# upperBoard.net
KiCad netlist of a schematic drawn in EAGLE
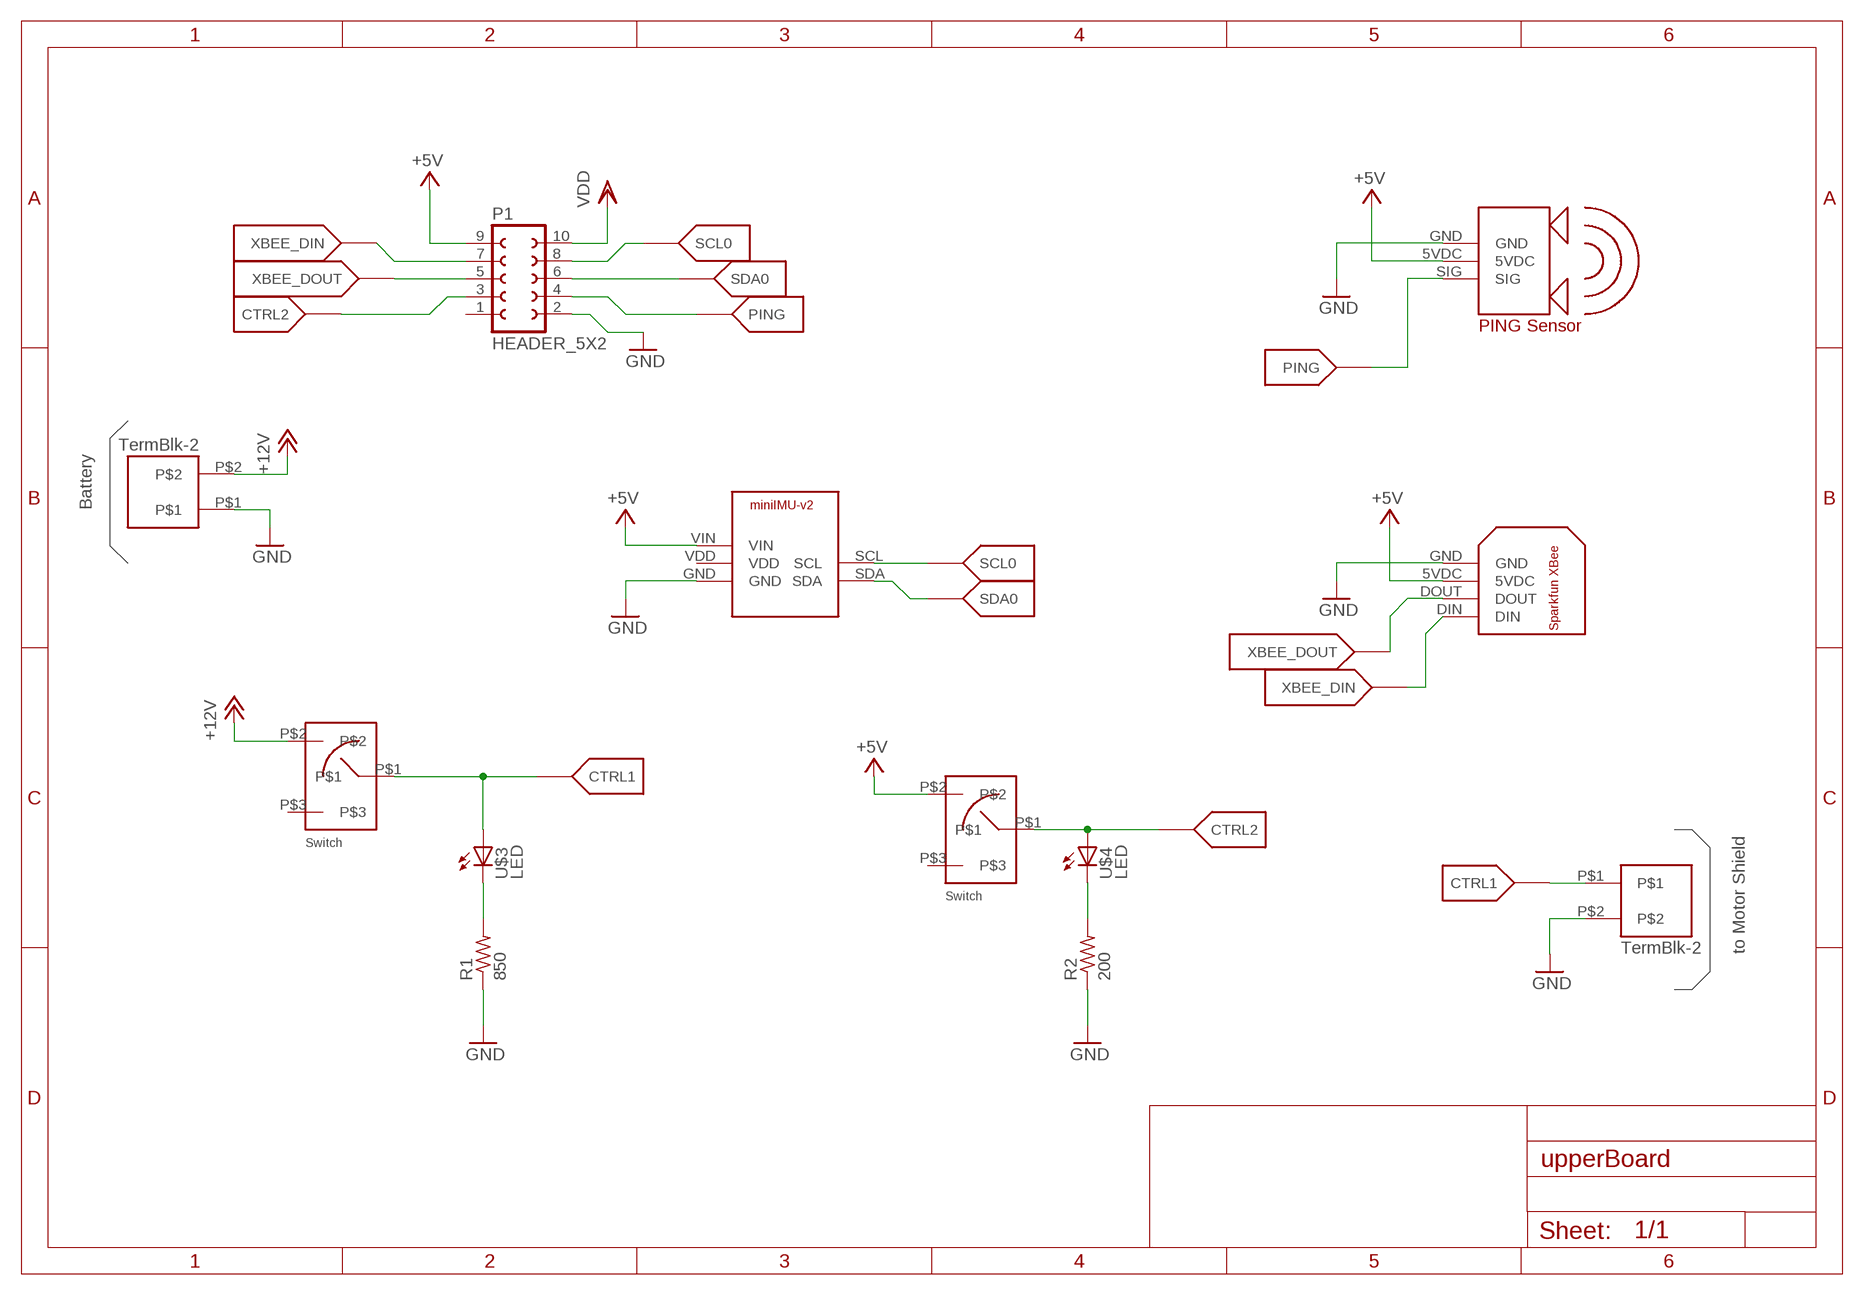
[diagram p0: schematic, sheet 1]

(export (version "E")
  (design (tool "Eeschema 10.0.6"))
  (components
    (comp (ref "P1")
      (value "HEADER_5X2")
      (footprint "eagle-import:HEADER_5X2")
      (libsource (lib "eagle-import") (part "HEADER_5X2"))
    )
    (comp (ref "R1")
      (value "850")
      (footprint "eagle-import:RESISTOR_PKG")
      (libsource (lib "eagle-import") (part "RESISTOR"))
    )
    (comp (ref "R2")
      (value "200")
      (footprint "eagle-import:RESISTOR_PKG")
      (libsource (lib "eagle-import") (part "RESISTOR"))
    )
    (comp (ref "U$1")
      (value "SWITCH-SPST")
      (footprint "eagle-import:SWITCH-SPST")
      (libsource (lib "eagle-import") (part "SWITCH-SPST"))
    )
    (comp (ref "U$2")
      (value "SWITCH-SPST")
      (footprint "eagle-import:SWITCH-SPST")
      (libsource (lib "eagle-import") (part "SWITCH-SPST"))
    )
    (comp (ref "U$3")
      (value "LED")
      (footprint "eagle-import:LED_PKG")
      (libsource (lib "eagle-import") (part "LED"))
    )
    (comp (ref "U$4")
      (value "LED")
      (footprint "eagle-import:LED_PKG")
      (libsource (lib "eagle-import") (part "LED"))
    )
    (comp (ref "U$7")
      (value "POLOLU_MINIIMU9_V2")
      (footprint "eagle-import:POLOLU_IMU9V2")
      (libsource (lib "eagle-import") (part "POLOLU_MINIIMU9_V2"))
    )
    (comp (ref "U$8")
      (value "SPARKFUNXBEE")
      (footprint "eagle-import:SPARKFUNXBEE")
      (libsource (lib "eagle-import") (part "SPARKFUNXBEE"))
    )
    (comp (ref "U$9")
      (value "PARALLAX_PING")
      (footprint "eagle-import:PING")
      (libsource (lib "eagle-import") (part "PARALLAX_PING"))
    )
    (comp (ref "U$16")
      (value "TB2")
      (footprint "eagle-import:TB2_PKG")
      (libsource (lib "eagle-import") (part "TB2"))
    )
    (comp (ref "U$18")
      (value "TB2")
      (footprint "eagle-import:TB2_PKG")
      (libsource (lib "eagle-import") (part "TB2"))
    )
  )
  (nets
    (net (code "1") (name "+5V") (class "Default")
      (node (ref "P1") (pin "9") (pinfunction "9_9") (pintype "passive"))
      (node (ref "U$2") (pin "P$2") (pinfunction "P$2_P$2") (pintype "bidirectional"))
      (node (ref "U$7") (pin "VIN") (pinfunction "VIN_VIN") (pintype "bidirectional"))
      (node (ref "U$8") (pin "5VDC") (pinfunction "5VDC_5VDC") (pintype "bidirectional"))
      (node (ref "U$9") (pin "5VDC") (pinfunction "5VDC_5VDC") (pintype "bidirectional"))
    )
    (net (code "2") (name "+12V") (class "Default")
      (node (ref "U$1") (pin "P$2") (pinfunction "P$2_P$2") (pintype "bidirectional"))
      (node (ref "U$16") (pin "P$2") (pinfunction "P$2_P$2") (pintype "bidirectional"))
    )
    (net (code "3") (name "CTRL1") (class "Default")
      (node (ref "U$1") (pin "P$1") (pinfunction "P$1_P$1") (pintype "bidirectional"))
      (node (ref "U$18") (pin "P$1") (pinfunction "P$1_P$1") (pintype "bidirectional"))
      (node (ref "U$3") (pin "A") (pinfunction "A_A") (pintype "passive"))
    )
    (net (code "4") (name "CTRL2") (class "Default")
      (node (ref "P1") (pin "3") (pinfunction "3_3") (pintype "passive"))
      (node (ref "U$2") (pin "P$1") (pinfunction "P$1_P$1") (pintype "bidirectional"))
      (node (ref "U$4") (pin "A") (pinfunction "A_A") (pintype "passive"))
    )
    (net (code "5") (name "GND") (class "Default")
      (node (ref "P1") (pin "2") (pinfunction "2_2") (pintype "passive"))
      (node (ref "R1") (pin "1") (pinfunction "1_1") (pintype "passive"))
      (node (ref "R2") (pin "1") (pinfunction "1_1") (pintype "passive"))
      (node (ref "U$16") (pin "P$1") (pinfunction "P$1_P$1") (pintype "bidirectional"))
      (node (ref "U$18") (pin "P$2") (pinfunction "P$2_P$2") (pintype "bidirectional"))
      (node (ref "U$7") (pin "GND") (pinfunction "GND_GND") (pintype "bidirectional"))
      (node (ref "U$8") (pin "GND") (pinfunction "GND_GND") (pintype "bidirectional"))
      (node (ref "U$9") (pin "GND") (pinfunction "GND_GND") (pintype "bidirectional"))
    )
    (net (code "6") (name "Net-(U$3-C)") (class "Default")
      (node (ref "R1") (pin "2") (pinfunction "2_2") (pintype "passive"))
      (node (ref "U$3") (pin "K") (pinfunction "C_K") (pintype "passive"))
    )
    (net (code "7") (name "Net-(U$4-C)") (class "Default")
      (node (ref "R2") (pin "2") (pinfunction "2_2") (pintype "passive"))
      (node (ref "U$4") (pin "K") (pinfunction "C_K") (pintype "passive"))
    )
    (net (code "8") (name "PING") (class "Default")
      (node (ref "P1") (pin "4") (pinfunction "4_4") (pintype "passive"))
      (node (ref "U$9") (pin "SIG") (pinfunction "SIG_SIG") (pintype "bidirectional"))
    )
    (net (code "9") (name "SCL0") (class "Default")
      (node (ref "P1") (pin "8") (pinfunction "8_8") (pintype "passive"))
      (node (ref "U$7") (pin "SCL") (pinfunction "SCL_SCL") (pintype "bidirectional"))
    )
    (net (code "10") (name "SDA0") (class "Default")
      (node (ref "P1") (pin "6") (pinfunction "6_6") (pintype "passive"))
      (node (ref "U$7") (pin "SDA") (pinfunction "SDA_SDA") (pintype "bidirectional"))
    )
    (net (code "11") (name "VDD") (class "Default")
      (node (ref "P1") (pin "10") (pinfunction "10_10") (pintype "passive"))
    )
    (net (code "12") (name "XBEE_DIN") (class "Default")
      (node (ref "P1") (pin "7") (pinfunction "7_7") (pintype "passive"))
      (node (ref "U$8") (pin "DIN") (pinfunction "DIN_DIN") (pintype "bidirectional"))
    )
    (net (code "13") (name "XBEE_DOUT") (class "Default")
      (node (ref "P1") (pin "5") (pinfunction "5_5") (pintype "passive"))
      (node (ref "U$8") (pin "DOUT") (pinfunction "DOUT_DOUT") (pintype "bidirectional"))
    )
    (net (code "14") (name "unconnected-(P1-Pad1)") (class "Default")
      (node (ref "P1") (pin "1") (pinfunction "1_1") (pintype "passive"))
    )
    (net (code "15") (name "unconnected-(U$1-PadP$3)") (class "Default")
      (node (ref "U$1") (pin "P$3") (pinfunction "P$3_P$3") (pintype "bidirectional"))
    )
    (net (code "16") (name "unconnected-(U$2-PadP$3)") (class "Default")
      (node (ref "U$2") (pin "P$3") (pinfunction "P$3_P$3") (pintype "bidirectional"))
    )
    (net (code "17") (name "unconnected-(U$7-PadVDD)") (class "Default")
      (node (ref "U$7") (pin "VDD") (pinfunction "VDD_VDD") (pintype "bidirectional"))
    )
  )
)
